# TSOC-USBUART1-3-2.net
KiCad netlist of a schematic drawn in EAGLE
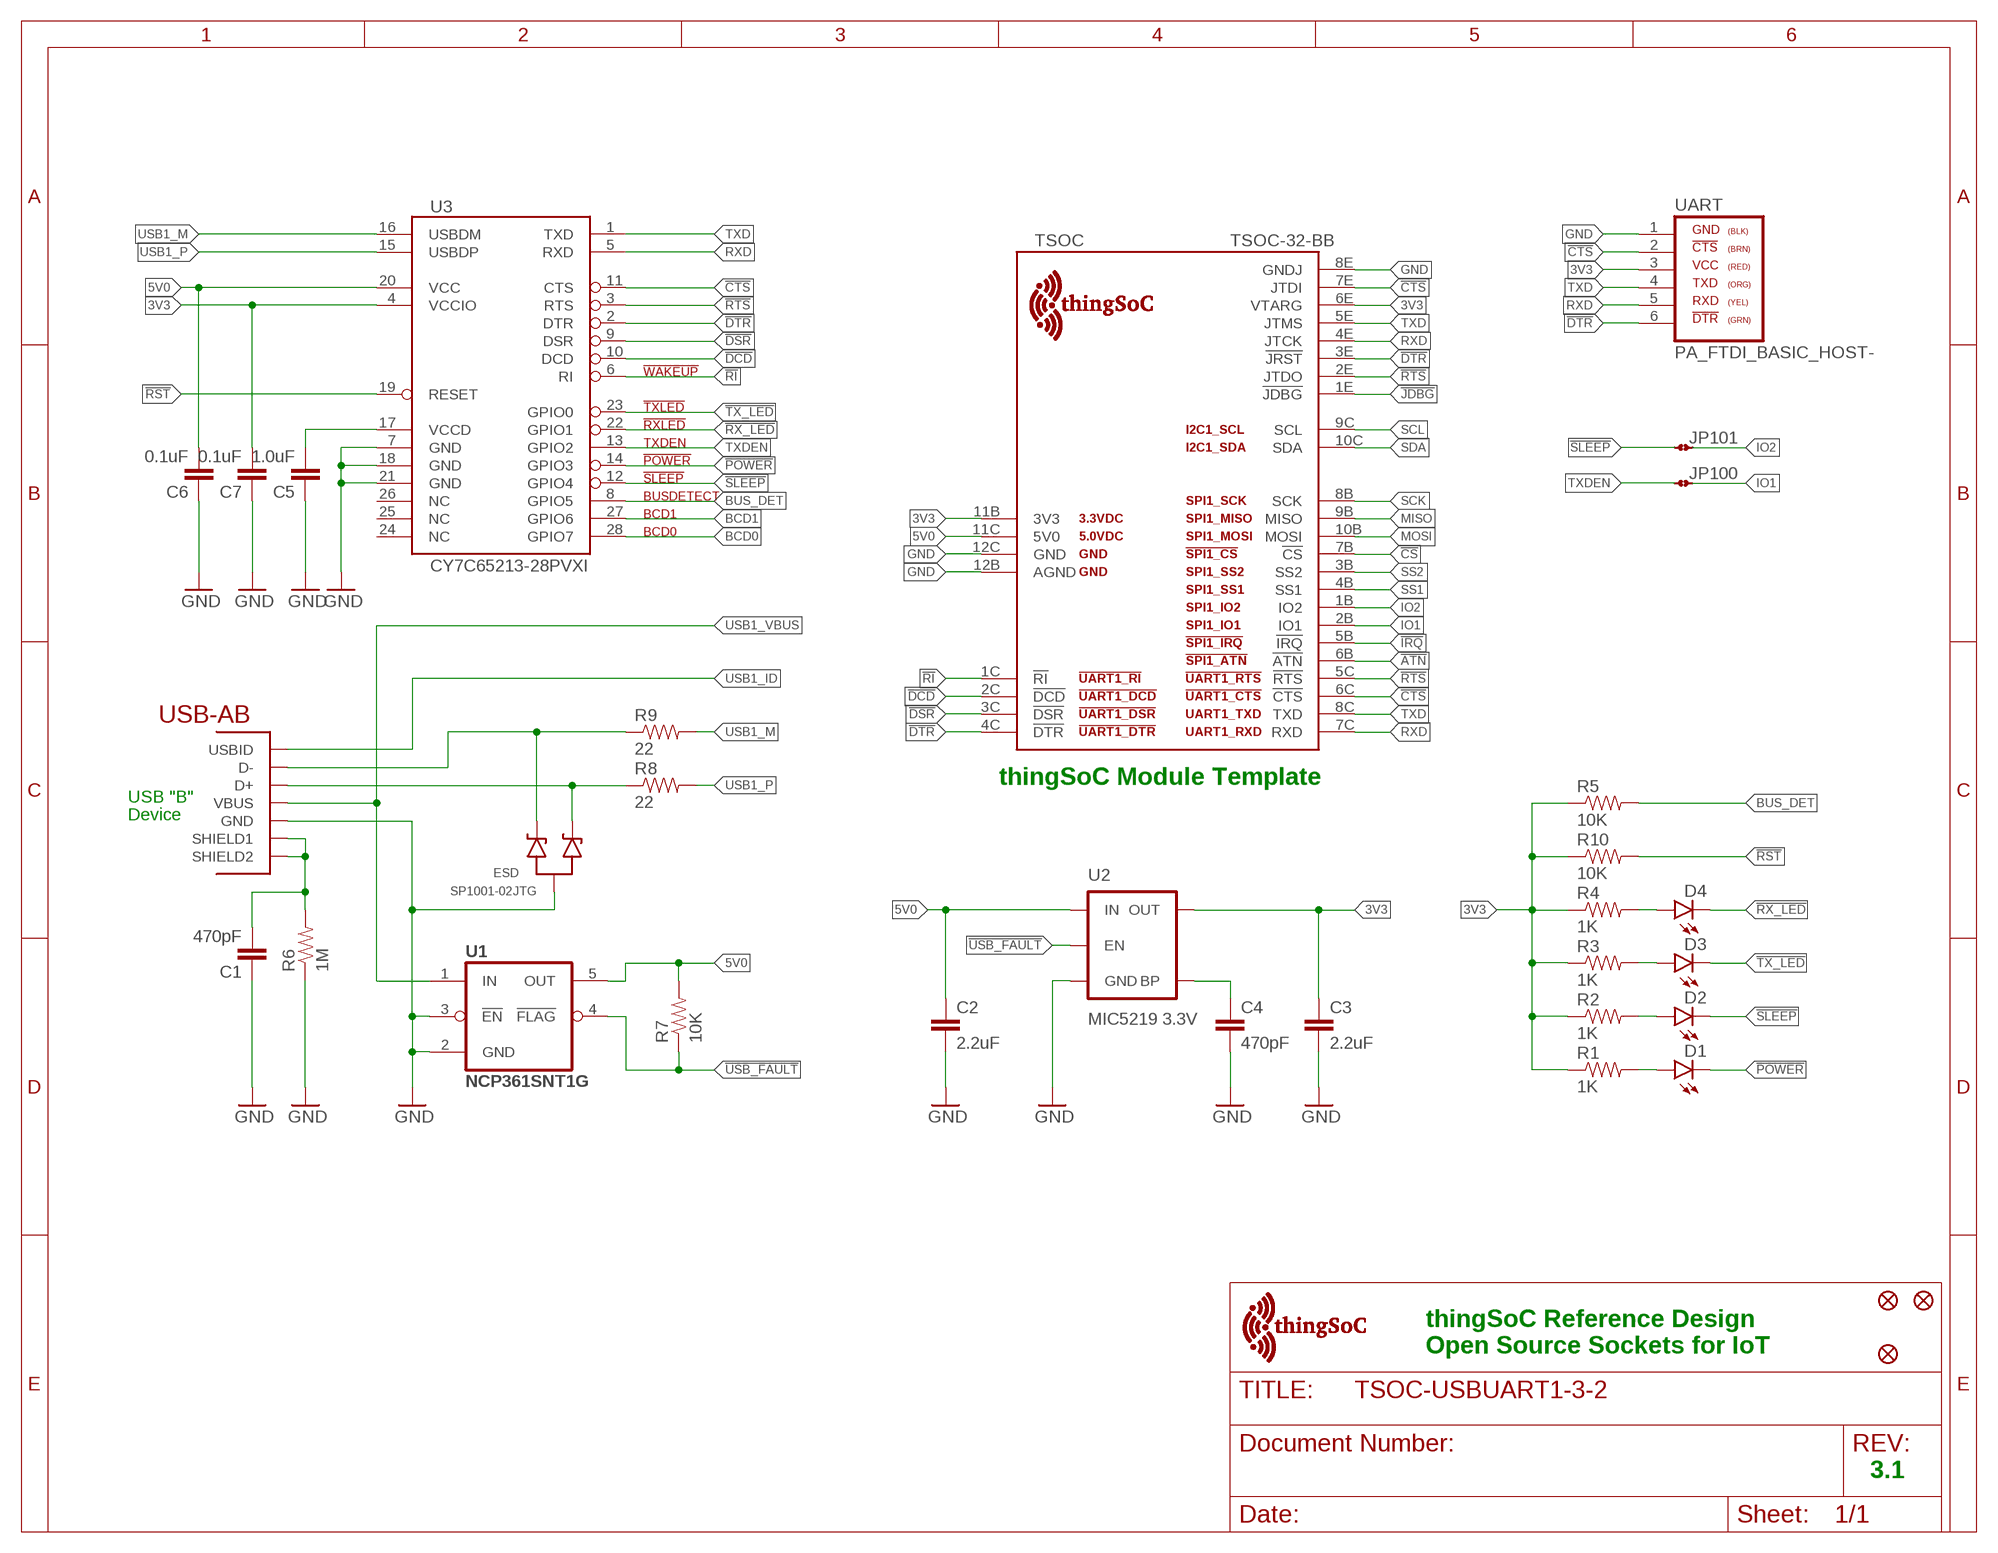
[diagram p0: schematic, sheet 1]

(export (version "E")
  (design (tool "Eeschema 10.0.6"))
  (components
    (comp (ref "C1")
      (value "470pF")
      (footprint "eagle-import:0603-CAP")
      (libsource (lib "eagle-import") (part "CAP0603-CAP"))
    )
    (comp (ref "C2")
      (value "2.2uF")
      (footprint "eagle-import:0603-CAP")
      (libsource (lib "eagle-import") (part "CAP0603-CAP"))
    )
    (comp (ref "C3")
      (value "2.2uF")
      (footprint "eagle-import:0603-CAP")
      (libsource (lib "eagle-import") (part "CAP0603-CAP"))
    )
    (comp (ref "C4")
      (value "470pF")
      (footprint "eagle-import:0603-CAP")
      (libsource (lib "eagle-import") (part "CAP0603-CAP"))
    )
    (comp (ref "C5")
      (value "1.0uF")
      (footprint "eagle-import:0603-CAP")
      (libsource (lib "eagle-import") (part "CAP0603-CAP"))
    )
    (comp (ref "C6")
      (value "0.1uF")
      (footprint "eagle-import:0603-CAP")
      (libsource (lib "eagle-import") (part "CAP0603-CAP"))
    )
    (comp (ref "C7")
      (value "0.1uF")
      (footprint "eagle-import:0603-CAP")
      (libsource (lib "eagle-import") (part "CAP0603-CAP"))
    )
    (comp (ref "D1")
      (value "LED0603")
      (footprint "eagle-import:LED-0603")
      (libsource (lib "eagle-import") (part "LED0603"))
    )
    (comp (ref "D2")
      (value "LED0603")
      (footprint "eagle-import:LED-0603")
      (libsource (lib "eagle-import") (part "LED0603"))
    )
    (comp (ref "D3")
      (value "LED0603")
      (footprint "eagle-import:LED-0603")
      (libsource (lib "eagle-import") (part "LED0603"))
    )
    (comp (ref "D4")
      (value "LED0603")
      (footprint "eagle-import:LED-0603")
      (libsource (lib "eagle-import") (part "LED0603"))
    )
    (comp (ref "ESD")
      (value "SP1001-02JTG")
      (footprint "eagle-import:SC70-3")
      (libsource (lib "eagle-import") (part "SP1001-02JTG"))
    )
    (comp (ref "FID1")
      (value "FIDUCIAL1.5X3")
      (footprint "eagle-import:FIDUCIAL-1.5X3")
      (libsource (lib "eagle-import") (part "FIDUCIAL1.5X3"))
    )
    (comp (ref "FID2")
      (value "FIDUCIAL1.5X3")
      (footprint "eagle-import:FIDUCIAL-1.5X3")
      (libsource (lib "eagle-import") (part "FIDUCIAL1.5X3"))
    )
    (comp (ref "FID3")
      (value "FIDUCIAL1.5X3")
      (footprint "eagle-import:FIDUCIAL-1.5X3")
      (libsource (lib "eagle-import") (part "FIDUCIAL1.5X3"))
    )
    (comp (ref "JP100")
      (value "JMP-2-NO")
      (footprint "eagle-import:JMP-2-NO")
      (libsource (lib "eagle-import") (part "JMP-2-NO"))
    )
    (comp (ref "JP101")
      (value "JMP-2-NO")
      (footprint "eagle-import:JMP-2-NO")
      (libsource (lib "eagle-import") (part "JMP-2-NO"))
    )
    (comp (ref "R1")
      (value "1K")
      (footprint "eagle-import:0603-RES")
      (libsource (lib "eagle-import") (part "RESISTOR0603-RES"))
    )
    (comp (ref "R2")
      (value "1K")
      (footprint "eagle-import:0603-RES")
      (libsource (lib "eagle-import") (part "RESISTOR0603-RES"))
    )
    (comp (ref "R3")
      (value "1K")
      (footprint "eagle-import:0603-RES")
      (libsource (lib "eagle-import") (part "RESISTOR0603-RES"))
    )
    (comp (ref "R4")
      (value "1K")
      (footprint "eagle-import:0603-RES")
      (libsource (lib "eagle-import") (part "RESISTOR0603-RES"))
    )
    (comp (ref "R5")
      (value "10K")
      (footprint "eagle-import:0603-RES")
      (libsource (lib "eagle-import") (part "RESISTOR0603-RES"))
    )
    (comp (ref "R6")
      (value "1M")
      (footprint "eagle-import:0603-RES")
      (libsource (lib "eagle-import") (part "RESISTOR0603-RES"))
    )
    (comp (ref "R7")
      (value "10K")
      (footprint "eagle-import:0603-RES")
      (libsource (lib "eagle-import") (part "RESISTOR0603-RES"))
    )
    (comp (ref "R8")
      (value "22")
      (footprint "eagle-import:0603-RES")
      (libsource (lib "eagle-import") (part "RESISTOR0603-RES"))
    )
    (comp (ref "R9")
      (value "22")
      (footprint "eagle-import:0603-RES")
      (libsource (lib "eagle-import") (part "RESISTOR0603-RES"))
    )
    (comp (ref "R10")
      (value "10K")
      (footprint "eagle-import:0603-RES")
      (libsource (lib "eagle-import") (part "RESISTOR0603-RES"))
    )
    (comp (ref "TSOC")
      (value "TSOC-32-BB")
      (footprint "eagle-import:TSOC-BB-S32")
      (libsource (lib "eagle-import") (part "TSOC-32-BB"))
    )
    (comp (ref "U$2")
      (value "TSOC-LOGO-MED")
      (footprint "eagle-import:TSOC-LOGO-MED")
      (libsource (lib "eagle-import") (part "TSOC-LOGO-MED"))
    )
    (comp (ref "U$101")
      (value "TSOC-LOGO-MED")
      (footprint "eagle-import:TSOC-LOGO-MED")
      (libsource (lib "eagle-import") (part "TSOC-LOGO-MED"))
    )
    (comp (ref "U1")
      (value "NCP361SNT1G")
      (footprint "eagle-import:SOP95P275X110-5N")
      (libsource (lib "eagle-import") (part "NCP361SNT1G"))
    )
    (comp (ref "U2")
      (value "MIC5219 3.3V")
      (footprint "eagle-import:SOT23-5")
      (libsource (lib "eagle-import") (part "V_REG_MIC52193.3V"))
    )
    (comp (ref "U3")
      (value "CY7C65213-28PVXI")
      (footprint "eagle-import:SSOP28DB")
      (libsource (lib "eagle-import") (part "CY7C65213-28PVXI"))
    )
    (comp (ref "UART")
      (value "PA_FTDI_BASIC_HOST-")
      (footprint "eagle-import:PA_FTDI_M5X1")
      (libsource (lib "eagle-import") (part "PA_FTDI_BASIC_HOST-"))
    )
    (comp (ref "USB1")
      (value "USB_AB")
      (footprint "eagle-import:USB-AB-MICRO-SMD")
      (libsource (lib "eagle-import") (part "USB_AB"))
    )
  )
  (nets
    (net (code "1") (name "/~{ATN}") (class "Default")
      (node (ref "TSOC") (pin "6B") (pinfunction "~{ATN}_6B") (pintype "bidirectional"))
    )
    (net (code "2") (name "/~{CS}") (class "Default")
      (node (ref "TSOC") (pin "7B") (pinfunction "~{CS}_7B") (pintype "bidirectional"))
    )
    (net (code "3") (name "/~{CTS}") (class "Default")
      (node (ref "TSOC") (pin "6C") (pinfunction "~{CTS}_6C") (pintype "bidirectional"))
      (node (ref "TSOC") (pin "7E") (pinfunction "JTDI_7E") (pintype "bidirectional"))
      (node (ref "U3") (pin "11") (pinfunction "CTS_11") (pintype "input"))
      (node (ref "UART") (pin "2") (pinfunction "2_2") (pintype "passive"))
    )
    (net (code "4") (name "/~{DCD}") (class "Default")
      (node (ref "TSOC") (pin "2C") (pinfunction "~{DCD}_2C") (pintype "bidirectional"))
      (node (ref "U3") (pin "10") (pinfunction "DCD_10") (pintype "input"))
    )
    (net (code "5") (name "/~{DSR}") (class "Default")
      (node (ref "TSOC") (pin "3C") (pinfunction "~{DSR}_3C") (pintype "bidirectional"))
      (node (ref "U3") (pin "9") (pinfunction "DSR_9") (pintype "input"))
    )
    (net (code "6") (name "/~{DTR}") (class "Default")
      (node (ref "TSOC") (pin "3E") (pinfunction "~{JRST}_3E") (pintype "bidirectional"))
      (node (ref "TSOC") (pin "4C") (pinfunction "~{DTR}_4C") (pintype "bidirectional"))
      (node (ref "U3") (pin "2") (pinfunction "DTR_2") (pintype "output"))
      (node (ref "UART") (pin "6") (pinfunction "6_6") (pintype "passive"))
    )
    (net (code "7") (name "/~{IRQ}") (class "Default")
      (node (ref "TSOC") (pin "5B") (pinfunction "~{IRQ}_5B") (pintype "bidirectional"))
    )
    (net (code "8") (name "/~{JDBG}") (class "Default")
      (node (ref "TSOC") (pin "1E") (pinfunction "~{JDBG}_1E") (pintype "bidirectional"))
    )
    (net (code "9") (name "/~{POWER}") (class "Default")
      (node (ref "D1") (pin "C") (pinfunction "C_C") (pintype "passive"))
      (node (ref "U3") (pin "14") (pinfunction "GPIO3_14") (pintype "output"))
    )
    (net (code "10") (name "/~{RI}") (class "Default")
      (node (ref "TSOC") (pin "1C") (pinfunction "~{RI}_1C") (pintype "bidirectional"))
      (node (ref "U3") (pin "6") (pinfunction "RI_6") (pintype "input"))
    )
    (net (code "11") (name "/~{RST}") (class "Default")
      (node (ref "R10") (pin "2") (pinfunction "2_2") (pintype "passive"))
      (node (ref "U3") (pin "19") (pinfunction "RESET_19") (pintype "input"))
    )
    (net (code "12") (name "/~{RTS}") (class "Default")
      (node (ref "TSOC") (pin "2E") (pinfunction "JTDO_2E") (pintype "bidirectional"))
      (node (ref "TSOC") (pin "5C") (pinfunction "~{RTS}_5C") (pintype "bidirectional"))
      (node (ref "U3") (pin "3") (pinfunction "RTS_3") (pintype "output"))
    )
    (net (code "13") (name "/~{RX_LED}") (class "Default")
      (node (ref "D4") (pin "C") (pinfunction "C_C") (pintype "passive"))
      (node (ref "U3") (pin "22") (pinfunction "GPIO1_22") (pintype "output"))
    )
    (net (code "14") (name "/~{SLEEP}") (class "Default")
      (node (ref "D2") (pin "C") (pinfunction "C_C") (pintype "passive"))
      (node (ref "JP101") (pin "1") (pinfunction "1_1") (pintype "passive"))
      (node (ref "U3") (pin "12") (pinfunction "GPIO4_12") (pintype "input"))
    )
    (net (code "15") (name "/~{TX_LED}") (class "Default")
      (node (ref "D3") (pin "C") (pinfunction "C_C") (pintype "passive"))
      (node (ref "U3") (pin "23") (pinfunction "GPIO0_23") (pintype "output"))
    )
    (net (code "16") (name "/~{USB_FAULT}") (class "Default")
      (node (ref "R7") (pin "1") (pinfunction "1_1") (pintype "passive"))
      (node (ref "U1") (pin "4") (pinfunction "~{FLAG}_4") (pintype "input"))
      (node (ref "U2") (pin "3") (pinfunction "EN_3") (pintype "input"))
    )
    (net (code "17") (name "3V3") (class "Default")
      (node (ref "C3") (pin "1") (pinfunction "1_1") (pintype "passive"))
      (node (ref "C7") (pin "2") (pinfunction "2_2") (pintype "passive"))
      (node (ref "R1") (pin "1") (pinfunction "1_1") (pintype "passive"))
      (node (ref "R10") (pin "1") (pinfunction "1_1") (pintype "passive"))
      (node (ref "R2") (pin "1") (pinfunction "1_1") (pintype "passive"))
      (node (ref "R3") (pin "1") (pinfunction "1_1") (pintype "passive"))
      (node (ref "R4") (pin "1") (pinfunction "1_1") (pintype "passive"))
      (node (ref "R5") (pin "1") (pinfunction "1_1") (pintype "passive"))
      (node (ref "TSOC") (pin "11B") (pinfunction "3V3_11B") (pintype "bidirectional"))
      (node (ref "TSOC") (pin "6E") (pinfunction "VTARG_6E") (pintype "bidirectional"))
      (node (ref "U2") (pin "5") (pinfunction "OUT_5") (pintype "passive"))
      (node (ref "U3") (pin "4") (pinfunction "VCCIO_4") (pintype "power_in"))
      (node (ref "UART") (pin "3") (pinfunction "3_3") (pintype "passive"))
    )
    (net (code "18") (name "5V0") (class "Default")
      (node (ref "C2") (pin "1") (pinfunction "1_1") (pintype "passive"))
      (node (ref "C6") (pin "2") (pinfunction "2_2") (pintype "passive"))
      (node (ref "R7") (pin "2") (pinfunction "2_2") (pintype "passive"))
      (node (ref "TSOC") (pin "11C") (pinfunction "5V0_11C") (pintype "bidirectional"))
      (node (ref "U1") (pin "5") (pinfunction "OUT_5") (pintype "output"))
      (node (ref "U2") (pin "1") (pinfunction "IN_1") (pintype "input"))
      (node (ref "U3") (pin "20") (pinfunction "VCC_20") (pintype "power_in"))
    )
    (net (code "19") (name "BCD0") (class "Default")
      (node (ref "U3") (pin "28") (pinfunction "GPIO7_28") (pintype "output"))
    )
    (net (code "20") (name "BCD1") (class "Default")
      (node (ref "U3") (pin "27") (pinfunction "GPIO6_27") (pintype "output"))
    )
    (net (code "21") (name "BUS_DET") (class "Default")
      (node (ref "R5") (pin "2") (pinfunction "2_2") (pintype "passive"))
      (node (ref "U3") (pin "8") (pinfunction "GPIO5_8") (pintype "input"))
    )
    (net (code "22") (name "GND") (class "Default")
      (node (ref "C1") (pin "1") (pinfunction "1_1") (pintype "passive"))
      (node (ref "C2") (pin "2") (pinfunction "2_2") (pintype "passive"))
      (node (ref "C3") (pin "2") (pinfunction "2_2") (pintype "passive"))
      (node (ref "C4") (pin "2") (pinfunction "2_2") (pintype "passive"))
      (node (ref "C5") (pin "1") (pinfunction "1_1") (pintype "passive"))
      (node (ref "C6") (pin "1") (pinfunction "1_1") (pintype "passive"))
      (node (ref "C7") (pin "1") (pinfunction "1_1") (pintype "passive"))
      (node (ref "ESD") (pin "3") (pinfunction "A_3") (pintype "passive"))
      (node (ref "R6") (pin "1") (pinfunction "1_1") (pintype "passive"))
      (node (ref "TSOC") (pin "12B") (pinfunction "AGND_12B") (pintype "bidirectional"))
      (node (ref "TSOC") (pin "12C") (pinfunction "GND_12C") (pintype "bidirectional"))
      (node (ref "TSOC") (pin "8E") (pinfunction "GNDJ_8E") (pintype "bidirectional"))
      (node (ref "U1") (pin "2") (pinfunction "GND_2") (pintype "passive"))
      (node (ref "U1") (pin "3") (pinfunction "~{EN}_3") (pintype "input"))
      (node (ref "U2") (pin "2") (pinfunction "GND_2") (pintype "input"))
      (node (ref "U3") (pin "18") (pinfunction "GND_18") (pintype "power_in"))
      (node (ref "U3") (pin "21") (pinfunction "GND_21") (pintype "power_in"))
      (node (ref "U3") (pin "7") (pinfunction "GND_7") (pintype "power_in"))
      (node (ref "UART") (pin "1") (pinfunction "1_1") (pintype "passive"))
      (node (ref "USB1") (pin "GND") (pinfunction "GND_GND") (pintype "bidirectional"))
    )
    (net (code "23") (name "IO1") (class "Default")
      (node (ref "JP100") (pin "2") (pinfunction "2_2") (pintype "passive"))
      (node (ref "TSOC") (pin "2B") (pinfunction "IO1_2B") (pintype "bidirectional"))
    )
    (net (code "24") (name "IO2") (class "Default")
      (node (ref "JP101") (pin "2") (pinfunction "2_2") (pintype "passive"))
      (node (ref "TSOC") (pin "1B") (pinfunction "IO2_1B") (pintype "bidirectional"))
    )
    (net (code "25") (name "MISO") (class "Default")
      (node (ref "TSOC") (pin "9B") (pinfunction "MISO_9B") (pintype "bidirectional"))
    )
    (net (code "26") (name "MOSI") (class "Default")
      (node (ref "TSOC") (pin "10B") (pinfunction "MOSI_10B") (pintype "bidirectional"))
    )
    (net (code "27") (name "Net-(C1-Pad2)") (class "Default")
      (node (ref "C1") (pin "2") (pinfunction "2_2") (pintype "passive"))
      (node (ref "R6") (pin "2") (pinfunction "2_2") (pintype "passive"))
      (node (ref "USB1") (pin "SHIELD1") (pinfunction "SHIELD1_SHIELD1") (pintype "bidirectional"))
      (node (ref "USB1") (pin "SHIELD2") (pinfunction "SHIELD2_SHIELD2") (pintype "bidirectional"))
    )
    (net (code "28") (name "Net-(D1-PadA)") (class "Default")
      (node (ref "D1") (pin "A") (pinfunction "A_A") (pintype "passive"))
      (node (ref "R1") (pin "2") (pinfunction "2_2") (pintype "passive"))
    )
    (net (code "29") (name "Net-(D2-PadA)") (class "Default")
      (node (ref "D2") (pin "A") (pinfunction "A_A") (pintype "passive"))
      (node (ref "R2") (pin "2") (pinfunction "2_2") (pintype "passive"))
    )
    (net (code "30") (name "Net-(D3-PadA)") (class "Default")
      (node (ref "D3") (pin "A") (pinfunction "A_A") (pintype "passive"))
      (node (ref "R3") (pin "2") (pinfunction "2_2") (pintype "passive"))
    )
    (net (code "31") (name "Net-(D4-PadA)") (class "Default")
      (node (ref "D4") (pin "A") (pinfunction "A_A") (pintype "passive"))
      (node (ref "R4") (pin "2") (pinfunction "2_2") (pintype "passive"))
    )
    (net (code "32") (name "Net-(ESD-C1)") (class "Default")
      (node (ref "ESD") (pin "1") (pinfunction "C1_1") (pintype "passive"))
      (node (ref "R8") (pin "1") (pinfunction "1_1") (pintype "passive"))
      (node (ref "USB1") (pin "D+") (pinfunction "D+_D+") (pintype "bidirectional"))
    )
    (net (code "33") (name "Net-(ESD-C2)") (class "Default")
      (node (ref "ESD") (pin "2") (pinfunction "C2_2") (pintype "passive"))
      (node (ref "R9") (pin "1") (pinfunction "1_1") (pintype "passive"))
      (node (ref "USB1") (pin "D-") (pinfunction "D-_D-") (pintype "bidirectional"))
    )
    (net (code "34") (name "Net-(U2-BP)") (class "Default")
      (node (ref "C4") (pin "1") (pinfunction "1_1") (pintype "passive"))
      (node (ref "U2") (pin "4") (pinfunction "BP_4") (pintype "input"))
    )
    (net (code "35") (name "Net-(U3-VCCD)") (class "Default")
      (node (ref "C5") (pin "2") (pinfunction "2_2") (pintype "passive"))
      (node (ref "U3") (pin "17") (pinfunction "VCCD_17") (pintype "power_in"))
    )
    (net (code "36") (name "RXD") (class "Default")
      (node (ref "TSOC") (pin "4E") (pinfunction "JTCK_4E") (pintype "bidirectional"))
      (node (ref "TSOC") (pin "7C") (pinfunction "RXD_7C") (pintype "bidirectional"))
      (node (ref "U3") (pin "5") (pinfunction "RXD_5") (pintype "input"))
      (node (ref "UART") (pin "5") (pinfunction "5_5") (pintype "passive"))
    )
    (net (code "37") (name "SCK") (class "Default")
      (node (ref "TSOC") (pin "8B") (pinfunction "SCK_8B") (pintype "bidirectional"))
    )
    (net (code "38") (name "SCL") (class "Default")
      (node (ref "TSOC") (pin "9C") (pinfunction "SCL_9C") (pintype "bidirectional"))
    )
    (net (code "39") (name "SDA") (class "Default")
      (node (ref "TSOC") (pin "10C") (pinfunction "SDA_10C") (pintype "bidirectional"))
    )
    (net (code "40") (name "SS1") (class "Default")
      (node (ref "TSOC") (pin "4B") (pinfunction "SS1_4B") (pintype "bidirectional"))
    )
    (net (code "41") (name "SS2") (class "Default")
      (node (ref "TSOC") (pin "3B") (pinfunction "SS2_3B") (pintype "bidirectional"))
    )
    (net (code "42") (name "TXD") (class "Default")
      (node (ref "TSOC") (pin "5E") (pinfunction "JTMS_5E") (pintype "bidirectional"))
      (node (ref "TSOC") (pin "8C") (pinfunction "TXD_8C") (pintype "bidirectional"))
      (node (ref "U3") (pin "1") (pinfunction "TXD_1") (pintype "output"))
      (node (ref "UART") (pin "4") (pinfunction "4_4") (pintype "passive"))
    )
    (net (code "43") (name "TXDEN") (class "Default")
      (node (ref "JP100") (pin "1") (pinfunction "1_1") (pintype "passive"))
      (node (ref "U3") (pin "13") (pinfunction "GPIO2_13") (pintype "output"))
    )
    (net (code "44") (name "USB1_ID") (class "Default")
      (node (ref "USB1") (pin "ID") (pinfunction "USBID_ID") (pintype "bidirectional"))
    )
    (net (code "45") (name "USB1_M") (class "Default")
      (node (ref "R9") (pin "2") (pinfunction "2_2") (pintype "passive"))
      (node (ref "U3") (pin "16") (pinfunction "USBDM_16") (pintype "bidirectional"))
    )
    (net (code "46") (name "USB1_P") (class "Default")
      (node (ref "R8") (pin "2") (pinfunction "2_2") (pintype "passive"))
      (node (ref "U3") (pin "15") (pinfunction "USBDP_15") (pintype "bidirectional"))
    )
    (net (code "47") (name "USB1_VBUS") (class "Default")
      (node (ref "U1") (pin "1") (pinfunction "IN_1") (pintype "power_in"))
      (node (ref "USB1") (pin "VBUS") (pinfunction "VBUS_VBUS") (pintype "bidirectional"))
    )
    (net (code "48") (name "unconnected-(U3-NC-Pad24)") (class "Default")
      (node (ref "U3") (pin "24") (pinfunction "NC_24") (pintype "no_connect"))
    )
    (net (code "49") (name "unconnected-(U3-NC-Pad25)") (class "Default")
      (node (ref "U3") (pin "25") (pinfunction "NC_25") (pintype "no_connect"))
    )
    (net (code "50") (name "unconnected-(U3-NC-Pad26)") (class "Default")
      (node (ref "U3") (pin "26") (pinfunction "NC_26") (pintype "no_connect"))
    )
  )
)
